# PIC18F4550.net
KiCad netlist of a schematic drawn in Altium Designer
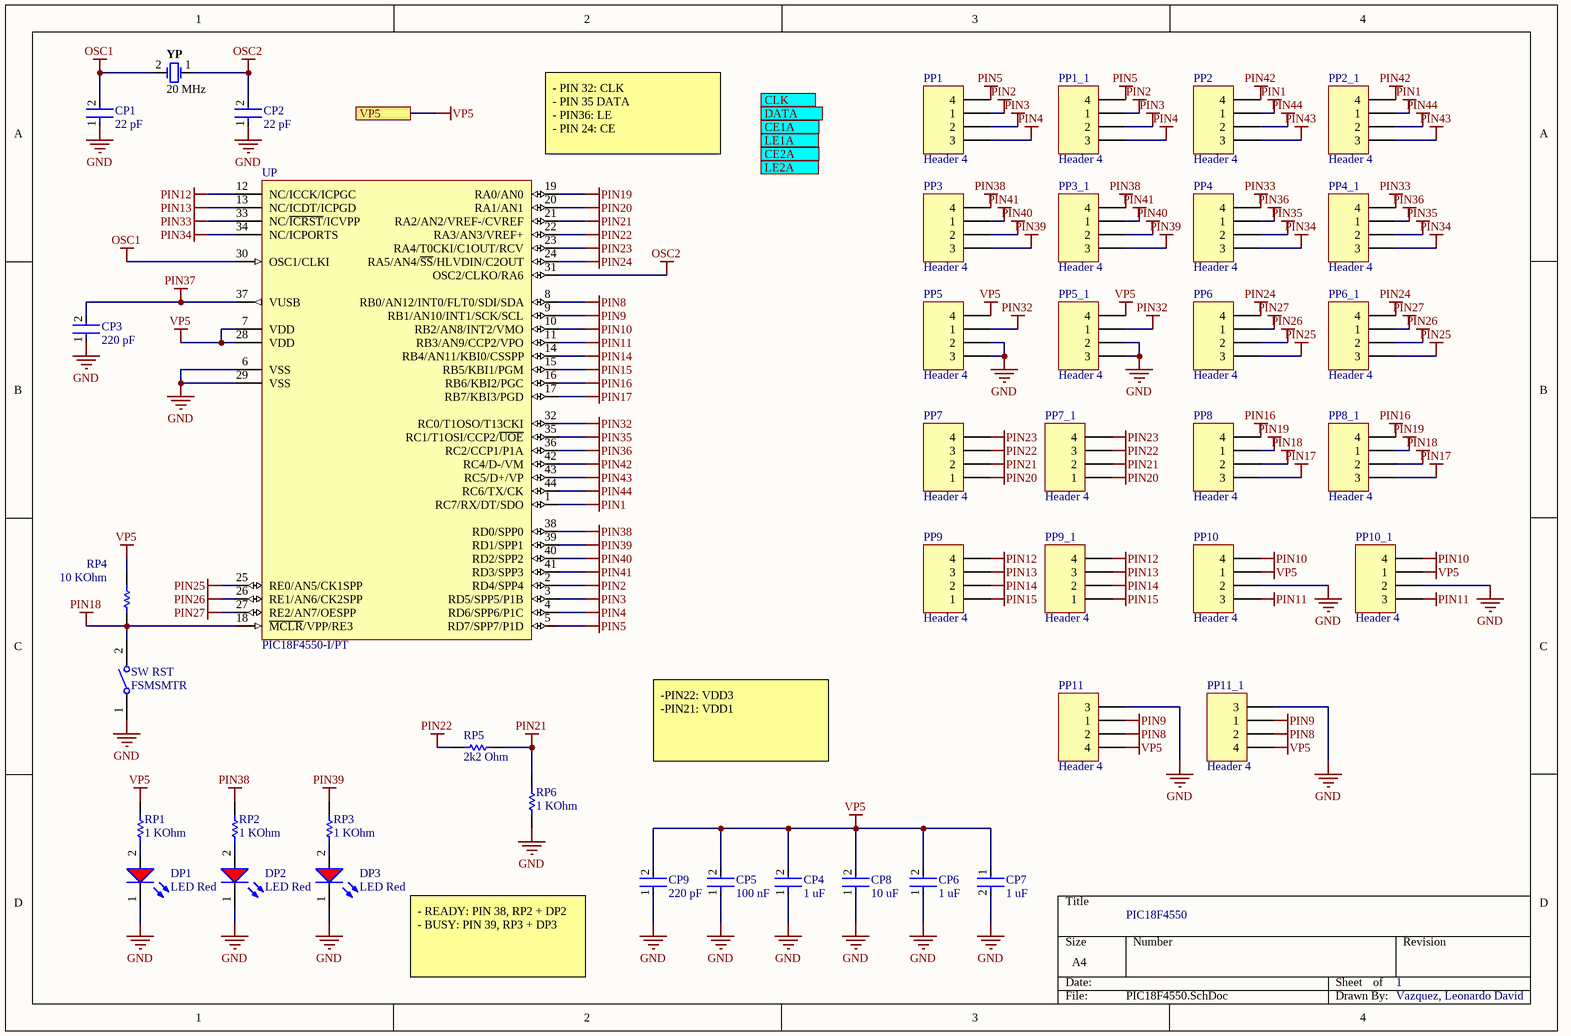
[diagram p0: PIC18F4550.SchDoc]

(export (version "E")
  (design (tool "Eeschema 10.0.6"))
  (components
    (comp (ref "CP1")
      (value "22 pF")
      (footprint "FP-CC0805-0_85-MFG")
      (description "CAP CER 0.1UF 50V X7R 0805")
      (fields (field (name "TOLERANCE") "0.1") (field (name "MANUFACTURER PART NUMBER") "CC0805KRX7R9BB104"))
      (libsource (lib "Altium Content Vault") (part "11868f565c42a9108669ba33697ecf6"))
    )
    (comp (ref "CP2")
      (value "22 pF")
      (footprint "FP-CC0805-0_85-MFG")
      (description "CAP CER 0.1UF 50V X7R 0805")
      (fields (field (name "TOLERANCE") "0.1") (field (name "MANUFACTURER PART NUMBER") "CC0805KRX7R9BB104"))
      (libsource (lib "Altium Content Vault") (part "11868f565c42a9108669ba33697ecf6"))
    )
    (comp (ref "CP3")
      (value "220 pF")
      (footprint "FP-CC0805-0_85-MFG")
      (description "CAP CER 0.1UF 50V X7R 0805")
      (fields (field (name "TOLERANCE") "0.1") (field (name "MANUFACTURER PART NUMBER") "CC0805KRX7R9BB104"))
      (libsource (lib "Altium Content Vault") (part "11868f565c42a9108669ba33697ecf6"))
    )
    (comp (ref "CP4")
      (value "1 uF")
      (footprint "FP-CC0805-0_85-MFG")
      (description "CAP CER 0.1UF 50V X7R 0805")
      (fields (field (name "TOLERANCE") "0.1") (field (name "MANUFACTURER PART NUMBER") "CC0805KRX7R9BB104"))
      (libsource (lib "Altium Content Vault") (part "11868f565c42a9108669ba33697ecf6"))
    )
    (comp (ref "CP5")
      (value "100 nF")
      (footprint "FP-CC0805-0_85-MFG")
      (description "CAP CER 0.1UF 50V X7R 0805")
      (fields (field (name "TOLERANCE") "0.1") (field (name "MANUFACTURER PART NUMBER") "CC0805KRX7R9BB104"))
      (libsource (lib "Altium Content Vault") (part "11868f565c42a9108669ba33697ecf6"))
    )
    (comp (ref "CP6")
      (value "1 uF")
      (footprint "FP-CC0805-0_85-MFG")
      (description "CAP CER 0.1UF 50V X7R 0805")
      (fields (field (name "TOLERANCE") "0.1") (field (name "MANUFACTURER PART NUMBER") "CC0805KRX7R9BB104"))
      (libsource (lib "Altium Content Vault") (part "11868f565c42a9108669ba33697ecf6"))
    )
    (comp (ref "CP7")
      (value "1 uF")
      (footprint "FP-CC0805-0_85-MFG")
      (description "CAP CER 0.1UF 50V X7R 0805")
      (fields (field (name "TOLERANCE") "0.1") (field (name "MANUFACTURER PART NUMBER") "CC0805KRX7R9BB104"))
      (libsource (lib "") (part "11868f565c42a9108669ba33697ecf6_1"))
    )
    (comp (ref "CP8")
      (value "10 uF")
      (footprint "FP-CC0805-0_85-MFG")
      (description "CAP CER 0.1UF 50V X7R 0805")
      (fields (field (name "TOLERANCE") "0.1") (field (name "MANUFACTURER PART NUMBER") "CC0805KRX7R9BB104"))
      (libsource (lib "Altium Content Vault") (part "11868f565c42a9108669ba33697ecf6"))
    )
    (comp (ref "CP9")
      (value "220 pF")
      (footprint "FP-CC0805-0_85-MFG")
      (description "CAP CER 0.1UF 50V X7R 0805")
      (fields (field (name "TOLERANCE") "0.1") (field (name "MANUFACTURER PART NUMBER") "CC0805KRX7R9BB104"))
      (libsource (lib "Altium Content Vault") (part "11868f565c42a9108669ba33697ecf6"))
    )
    (comp (ref "DP1")
      (value "LED Red")
      (footprint "WL-SMCW_0805_150080xx75000")
      (libsource (lib "Altium Content Vault") (part "LED_Red_2A-1K"))
    )
    (comp (ref "DP2")
      (value "LED Red")
      (footprint "WL-SMCW_0805_150080xx75000")
      (libsource (lib "Altium Content Vault") (part "LED_Red_2A-1K"))
    )
    (comp (ref "DP3")
      (value "LED Red")
      (footprint "WL-SMCW_0805_150080xx75000")
      (libsource (lib "Altium Content Vault") (part "LED_Red_2A-1K"))
    )
    (comp (ref "PP1")
      (value "Header 4")
      (footprint "HDR1X4")
      (description "Header, 4-Pin")
      (fields (field (name "PUBLISHER") "Altium Limited"))
      (libsource (lib "Miscellaneous Connectors") (part "Header 4"))
    )
    (comp (ref "PP1_1")
      (value "Header 4")
      (footprint "HDR1X4")
      (description "Header, 4-Pin")
      (fields (field (name "PUBLISHER") "Altium Limited"))
      (libsource (lib "Miscellaneous Connectors") (part "Header 4"))
    )
    (comp (ref "PP2")
      (value "Header 4")
      (footprint "HDR1X4")
      (description "Header, 4-Pin")
      (fields (field (name "PUBLISHER") "Altium Limited"))
      (libsource (lib "Miscellaneous Connectors") (part "Header 4"))
    )
    (comp (ref "PP2_1")
      (value "Header 4")
      (footprint "HDR1X4")
      (description "Header, 4-Pin")
      (fields (field (name "PUBLISHER") "Altium Limited"))
      (libsource (lib "Miscellaneous Connectors") (part "Header 4"))
    )
    (comp (ref "PP3")
      (value "Header 4")
      (footprint "HDR1X4")
      (description "Header, 4-Pin")
      (fields (field (name "PUBLISHER") "Altium Limited"))
      (libsource (lib "Miscellaneous Connectors") (part "Header 4"))
    )
    (comp (ref "PP3_1")
      (value "Header 4")
      (footprint "HDR1X4")
      (description "Header, 4-Pin")
      (fields (field (name "PUBLISHER") "Altium Limited"))
      (libsource (lib "Miscellaneous Connectors") (part "Header 4"))
    )
    (comp (ref "PP4")
      (value "Header 4")
      (footprint "HDR1X4")
      (description "Header, 4-Pin")
      (fields (field (name "PUBLISHER") "Altium Limited"))
      (libsource (lib "Miscellaneous Connectors") (part "Header 4"))
    )
    (comp (ref "PP4_1")
      (value "Header 4")
      (footprint "HDR1X4")
      (description "Header, 4-Pin")
      (fields (field (name "PUBLISHER") "Altium Limited"))
      (libsource (lib "Miscellaneous Connectors") (part "Header 4"))
    )
    (comp (ref "PP5")
      (value "Header 4")
      (footprint "HDR1X4")
      (description "Header, 4-Pin")
      (fields (field (name "PUBLISHER") "Altium Limited"))
      (libsource (lib "Miscellaneous Connectors") (part "Header 4"))
    )
    (comp (ref "PP5_1")
      (value "Header 4")
      (footprint "HDR1X4")
      (description "Header, 4-Pin")
      (fields (field (name "PUBLISHER") "Altium Limited"))
      (libsource (lib "Miscellaneous Connectors") (part "Header 4"))
    )
    (comp (ref "PP6")
      (value "Header 4")
      (footprint "HDR1X4")
      (description "Header, 4-Pin")
      (fields (field (name "PUBLISHER") "Altium Limited"))
      (libsource (lib "Miscellaneous Connectors") (part "Header 4"))
    )
    (comp (ref "PP6_1")
      (value "Header 4")
      (footprint "HDR1X4")
      (description "Header, 4-Pin")
      (fields (field (name "PUBLISHER") "Altium Limited"))
      (libsource (lib "Miscellaneous Connectors") (part "Header 4"))
    )
    (comp (ref "PP7")
      (value "Header 4")
      (footprint "HDR1X4")
      (description "Header, 4-Pin")
      (fields (field (name "PUBLISHER") "Altium Limited"))
      (libsource (lib "") (part "Header 4_2"))
    )
    (comp (ref "PP7_1")
      (value "Header 4")
      (footprint "HDR1X4")
      (description "Header, 4-Pin")
      (fields (field (name "PUBLISHER") "Altium Limited"))
      (libsource (lib "") (part "Header 4_2"))
    )
    (comp (ref "PP8")
      (value "Header 4")
      (footprint "HDR1X4")
      (description "Header, 4-Pin")
      (fields (field (name "PUBLISHER") "Altium Limited"))
      (libsource (lib "Miscellaneous Connectors") (part "Header 4"))
    )
    (comp (ref "PP8_1")
      (value "Header 4")
      (footprint "HDR1X4")
      (description "Header, 4-Pin")
      (fields (field (name "PUBLISHER") "Altium Limited"))
      (libsource (lib "Miscellaneous Connectors") (part "Header 4"))
    )
    (comp (ref "PP9")
      (value "Header 4")
      (footprint "HDR1X4")
      (description "Header, 4-Pin")
      (fields (field (name "PUBLISHER") "Altium Limited"))
      (libsource (lib "") (part "Header 4_2"))
    )
    (comp (ref "PP9_1")
      (value "Header 4")
      (footprint "HDR1X4")
      (description "Header, 4-Pin")
      (fields (field (name "PUBLISHER") "Altium Limited"))
      (libsource (lib "") (part "Header 4_2"))
    )
    (comp (ref "PP10")
      (value "Header 4")
      (footprint "HDR1X4")
      (description "Header, 4-Pin")
      (fields (field (name "PUBLISHER") "Altium Limited"))
      (libsource (lib "Miscellaneous Connectors") (part "Header 4"))
    )
    (comp (ref "PP10_1")
      (value "Header 4")
      (footprint "HDR1X4")
      (description "Header, 4-Pin")
      (fields (field (name "PUBLISHER") "Altium Limited"))
      (libsource (lib "Miscellaneous Connectors") (part "Header 4"))
    )
    (comp (ref "PP11")
      (value "Header 4")
      (footprint "HDR1X4")
      (description "Header, 4-Pin")
      (fields (field (name "PUBLISHER") "Altium Limited"))
      (libsource (lib "") (part "Header 4_1"))
    )
    (comp (ref "PP11_1")
      (value "Header 4")
      (footprint "HDR1X4")
      (description "Header, 4-Pin")
      (fields (field (name "PUBLISHER") "Altium Limited"))
      (libsource (lib "") (part "Header 4_1"))
    )
    (comp (ref "RP1")
      (value "1 KOhm")
      (footprint "RESC2013X60X40ML20T25")
      (fields (field (name "MANUFACTURER") "Panasonic") (field (name "PART NUMBER") "ERA6AEB101V"))
      (libsource (lib "Altium Content Vault") (part "RES"))
    )
    (comp (ref "RP2")
      (value "1 KOhm")
      (footprint "RESC2013X60X40ML20T25")
      (fields (field (name "MANUFACTURER") "Panasonic") (field (name "PART NUMBER") "ERA6AEB101V"))
      (libsource (lib "Altium Content Vault") (part "RES"))
    )
    (comp (ref "RP3")
      (value "1 KOhm")
      (footprint "RESC2013X60X40ML20T25")
      (fields (field (name "MANUFACTURER") "Panasonic") (field (name "PART NUMBER") "ERA6AEB101V"))
      (libsource (lib "Altium Content Vault") (part "RES"))
    )
    (comp (ref "RP4")
      (value "10 KOhm")
      (footprint "RESC2013X60X40ML20T25")
      (fields (field (name "MANUFACTURER") "Panasonic") (field (name "PART NUMBER") "ERA6AEB101V"))
      (libsource (lib "Altium Content Vault") (part "RES"))
    )
    (comp (ref "RP5")
      (value "2k2 Ohm")
      (footprint "RESC2013X60X40ML20T25")
      (fields (field (name "MANUFACTURER") "Panasonic") (field (name "PART NUMBER") "ERA6AEB101V"))
      (libsource (lib "Altium Content Vault") (part "RES"))
    )
    (comp (ref "RP6")
      (value "1 KOhm")
      (footprint "RESC2013X60X40ML20T25")
      (fields (field (name "MANUFACTURER") "Panasonic") (field (name "PART NUMBER") "ERA6AEB101V"))
      (libsource (lib "Altium Content Vault") (part "RES"))
    )
    (comp (ref "SW RST")
      (value "FSMSMTR")
      (footprint "TECO-FSMSMTR_V")
      (description "FSMSM Push Button Switch, 50 mA, -35 to 85 degC, 2-Pin SMD, RoHS, Tape and Reel")
      (fields (field (name "MANUFACTURER") "TE Connectivity"))
      (libsource (lib "Altium Content Vault") (part "SW-SPST-2_C"))
    )
    (comp (ref "UP")
      (value "PIC18F4550-I/PT")
      (footprint "TQFP-PT44_M")
      (libsource (lib "Altium Content Vault") (part "MC-8B-18F4550-SQ44A"))
    )
    (comp (ref "YP")
      (value "20 MHz")
      (footprint "FOX-FOXSLF160-20")
      (description "Resistance Weld Thru-Hole Crystal, 16 MHz, -20 to 70 degC, 2-Pin THD, RoHS, Bulk")
      (fields (field (name "TOLERANCE") "1%"))
      (libsource (lib "Altium Content Vault") (part "XTAL-1-2-2"))
    )
  )
  (nets
    (net (code "7") (name "GND") (class "Default")
      (node (ref "CP1") (pin "1") (pinfunction "1_1") (pintype "passive"))
      (node (ref "CP2") (pin "1") (pinfunction "1_1") (pintype "passive"))
      (node (ref "CP3") (pin "1") (pinfunction "1_1") (pintype "passive"))
      (node (ref "CP4") (pin "1") (pinfunction "1_1") (pintype "passive"))
      (node (ref "CP5") (pin "1") (pinfunction "1_1") (pintype "passive"))
      (node (ref "CP6") (pin "1") (pinfunction "1_1") (pintype "passive"))
      (node (ref "CP7") (pin "2") (pinfunction "2_2") (pintype "passive"))
      (node (ref "CP8") (pin "1") (pinfunction "1_1") (pintype "passive"))
      (node (ref "CP9") (pin "1") (pinfunction "1_1") (pintype "passive"))
      (node (ref "DP1") (pin "1") (pinfunction "K_1") (pintype "passive"))
      (node (ref "DP2") (pin "1") (pinfunction "K_1") (pintype "passive"))
      (node (ref "DP3") (pin "1") (pinfunction "K_1") (pintype "passive"))
      (node (ref "PP10") (pin "2") (pinfunction "2_2") (pintype "passive"))
      (node (ref "PP10_1") (pin "2") (pinfunction "2_2") (pintype "passive"))
      (node (ref "PP11") (pin "3") (pinfunction "3_3") (pintype "passive"))
      (node (ref "PP11_1") (pin "3") (pinfunction "3_3") (pintype "passive"))
      (node (ref "PP5") (pin "2") (pinfunction "2_2") (pintype "passive"))
      (node (ref "PP5") (pin "3") (pinfunction "3_3") (pintype "passive"))
      (node (ref "PP5_1") (pin "2") (pinfunction "2_2") (pintype "passive"))
      (node (ref "PP5_1") (pin "3") (pinfunction "3_3") (pintype "passive"))
      (node (ref "RP6") (pin "1") (pinfunction "1_1") (pintype "passive"))
      (node (ref "SW RST") (pin "1") (pinfunction "1_1") (pintype "passive"))
      (node (ref "UP") (pin "29") (pinfunction "VSS_29") (pintype "power_in"))
      (node (ref "UP") (pin "6") (pinfunction "VSS_6") (pintype "power_in"))
    )
    (net (code "8") (name "Net-(DP1-A)") (class "Default")
      (node (ref "DP1") (pin "2") (pinfunction "A_2") (pintype "passive"))
      (node (ref "RP1") (pin "1") (pinfunction "1_1") (pintype "passive"))
    )
    (net (code "9") (name "Net-(DP2-A)") (class "Default")
      (node (ref "DP2") (pin "2") (pinfunction "A_2") (pintype "passive"))
      (node (ref "RP2") (pin "1") (pinfunction "1_1") (pintype "passive"))
    )
    (net (code "10") (name "Net-(DP3-A)") (class "Default")
      (node (ref "DP3") (pin "2") (pinfunction "A_2") (pintype "passive"))
      (node (ref "RP3") (pin "1") (pinfunction "1_1") (pintype "passive"))
    )
    (net (code "11") (name "OSC1") (class "Default")
      (node (ref "CP1") (pin "2") (pinfunction "2_2") (pintype "passive"))
      (node (ref "UP") (pin "30") (pinfunction "OSC1/CLKI_30") (pintype "input"))
      (node (ref "YP") (pin "2") (pinfunction "2_2") (pintype "passive"))
    )
    (net (code "12") (name "OSC2") (class "Default")
      (node (ref "CP2") (pin "2") (pinfunction "2_2") (pintype "passive"))
      (node (ref "UP") (pin "31") (pinfunction "OSC2/CLKO/RA6_31") (pintype "bidirectional"))
      (node (ref "YP") (pin "1") (pinfunction "1_1") (pintype "passive"))
    )
    (net (code "13") (name "PIN1") (class "Default")
      (node (ref "PP2") (pin "1") (pinfunction "1_1") (pintype "passive"))
      (node (ref "PP2_1") (pin "1") (pinfunction "1_1") (pintype "passive"))
      (node (ref "UP") (pin "1") (pinfunction "RC7/RX/DT/SDO_1") (pintype "bidirectional"))
    )
    (net (code "14") (name "PIN2") (class "Default")
      (node (ref "PP1") (pin "1") (pinfunction "1_1") (pintype "passive"))
      (node (ref "PP1_1") (pin "1") (pinfunction "1_1") (pintype "passive"))
      (node (ref "UP") (pin "2") (pinfunction "RD4/SPP4_2") (pintype "bidirectional"))
    )
    (net (code "15") (name "PIN3") (class "Default")
      (node (ref "PP1") (pin "2") (pinfunction "2_2") (pintype "passive"))
      (node (ref "PP1_1") (pin "2") (pinfunction "2_2") (pintype "passive"))
      (node (ref "UP") (pin "3") (pinfunction "RD5/SPP5/P1B_3") (pintype "bidirectional"))
    )
    (net (code "16") (name "PIN4") (class "Default")
      (node (ref "PP1") (pin "3") (pinfunction "3_3") (pintype "passive"))
      (node (ref "PP1_1") (pin "3") (pinfunction "3_3") (pintype "passive"))
      (node (ref "UP") (pin "4") (pinfunction "RD6/SPP6/P1C_4") (pintype "bidirectional"))
    )
    (net (code "17") (name "PIN5") (class "Default")
      (node (ref "PP1") (pin "4") (pinfunction "4_4") (pintype "passive"))
      (node (ref "PP1_1") (pin "4") (pinfunction "4_4") (pintype "passive"))
      (node (ref "UP") (pin "5") (pinfunction "RD7/SPP7/P1D_5") (pintype "bidirectional"))
    )
    (net (code "18") (name "PIN8") (class "Default")
      (node (ref "PP11") (pin "2") (pinfunction "2_2") (pintype "passive"))
      (node (ref "PP11_1") (pin "2") (pinfunction "2_2") (pintype "passive"))
      (node (ref "UP") (pin "8") (pinfunction "RB0/AN12/INT0/FLT0/SDI/SDA_8") (pintype "bidirectional"))
    )
    (net (code "19") (name "PIN9") (class "Default")
      (node (ref "PP11") (pin "1") (pinfunction "1_1") (pintype "passive"))
      (node (ref "PP11_1") (pin "1") (pinfunction "1_1") (pintype "passive"))
      (node (ref "UP") (pin "9") (pinfunction "RB1/AN10/INT1/SCK/SCL_9") (pintype "bidirectional"))
    )
    (net (code "20") (name "PIN10") (class "Default")
      (node (ref "PP10") (pin "4") (pinfunction "4_4") (pintype "passive"))
      (node (ref "PP10_1") (pin "4") (pinfunction "4_4") (pintype "passive"))
      (node (ref "UP") (pin "10") (pinfunction "RB2/AN8/INT2/VMO_10") (pintype "bidirectional"))
    )
    (net (code "21") (name "PIN11") (class "Default")
      (node (ref "PP10") (pin "3") (pinfunction "3_3") (pintype "passive"))
      (node (ref "PP10_1") (pin "3") (pinfunction "3_3") (pintype "passive"))
      (node (ref "UP") (pin "11") (pinfunction "RB3/AN9/CCP2/VPO_11") (pintype "bidirectional"))
    )
    (net (code "22") (name "PIN12") (class "Default")
      (node (ref "PP9") (pin "4") (pinfunction "4_4") (pintype "passive"))
      (node (ref "PP9_1") (pin "4") (pinfunction "4_4") (pintype "passive"))
      (node (ref "UP") (pin "12") (pinfunction "NC/ICCK/ICPGC_12") (pintype "passive"))
    )
    (net (code "23") (name "PIN13") (class "Default")
      (node (ref "PP9") (pin "3") (pinfunction "3_3") (pintype "passive"))
      (node (ref "PP9_1") (pin "3") (pinfunction "3_3") (pintype "passive"))
      (node (ref "UP") (pin "13") (pinfunction "NC/ICDT/ICPGD_13") (pintype "passive"))
    )
    (net (code "24") (name "PIN14") (class "Default")
      (node (ref "PP9") (pin "2") (pinfunction "2_2") (pintype "passive"))
      (node (ref "PP9_1") (pin "2") (pinfunction "2_2") (pintype "passive"))
      (node (ref "UP") (pin "14") (pinfunction "RB4/AN11/KBI0/CSSPP_14") (pintype "bidirectional"))
    )
    (net (code "25") (name "PIN15") (class "Default")
      (node (ref "PP9") (pin "1") (pinfunction "1_1") (pintype "passive"))
      (node (ref "PP9_1") (pin "1") (pinfunction "1_1") (pintype "passive"))
      (node (ref "UP") (pin "15") (pinfunction "RB5/KBI1/PGM_15") (pintype "bidirectional"))
    )
    (net (code "26") (name "PIN16") (class "Default")
      (node (ref "PP8") (pin "4") (pinfunction "4_4") (pintype "passive"))
      (node (ref "PP8_1") (pin "4") (pinfunction "4_4") (pintype "passive"))
      (node (ref "UP") (pin "16") (pinfunction "RB6/KBI2/PGC_16") (pintype "bidirectional"))
    )
    (net (code "27") (name "PIN17") (class "Default")
      (node (ref "PP8") (pin "3") (pinfunction "3_3") (pintype "passive"))
      (node (ref "PP8_1") (pin "3") (pinfunction "3_3") (pintype "passive"))
      (node (ref "UP") (pin "17") (pinfunction "RB7/KBI3/PGD_17") (pintype "bidirectional"))
    )
    (net (code "28") (name "PIN18") (class "Default")
      (node (ref "PP8") (pin "2") (pinfunction "2_2") (pintype "passive"))
      (node (ref "PP8_1") (pin "2") (pinfunction "2_2") (pintype "passive"))
      (node (ref "RP4") (pin "1") (pinfunction "1_1") (pintype "passive"))
      (node (ref "SW RST") (pin "2") (pinfunction "2_2") (pintype "passive"))
      (node (ref "UP") (pin "18") (pinfunction "~{MCLR}/VPP/RE3_18") (pintype "input"))
    )
    (net (code "29") (name "PIN19") (class "Default")
      (node (ref "PP8") (pin "1") (pinfunction "1_1") (pintype "passive"))
      (node (ref "PP8_1") (pin "1") (pinfunction "1_1") (pintype "passive"))
      (node (ref "UP") (pin "19") (pinfunction "RA0/AN0_19") (pintype "bidirectional"))
    )
    (net (code "30") (name "PIN20") (class "Default")
      (node (ref "PP7") (pin "1") (pinfunction "1_1") (pintype "passive"))
      (node (ref "PP7_1") (pin "1") (pinfunction "1_1") (pintype "passive"))
      (node (ref "UP") (pin "20") (pinfunction "RA1/AN1_20") (pintype "bidirectional"))
    )
    (net (code "31") (name "PIN21") (class "Default")
      (node (ref "PP7") (pin "2") (pinfunction "2_2") (pintype "passive"))
      (node (ref "PP7_1") (pin "2") (pinfunction "2_2") (pintype "passive"))
      (node (ref "RP5") (pin "1") (pinfunction "1_1") (pintype "passive"))
      (node (ref "RP6") (pin "2") (pinfunction "2_2") (pintype "passive"))
      (node (ref "UP") (pin "21") (pinfunction "RA2/AN2/VREF-/CVREF_21") (pintype "bidirectional"))
    )
    (net (code "32") (name "PIN22") (class "Default")
      (node (ref "PP7") (pin "3") (pinfunction "3_3") (pintype "passive"))
      (node (ref "PP7_1") (pin "3") (pinfunction "3_3") (pintype "passive"))
      (node (ref "RP5") (pin "2") (pinfunction "2_2") (pintype "passive"))
      (node (ref "UP") (pin "22") (pinfunction "RA3/AN3/VREF+_22") (pintype "bidirectional"))
    )
    (net (code "33") (name "PIN23") (class "Default")
      (node (ref "PP7") (pin "4") (pinfunction "4_4") (pintype "passive"))
      (node (ref "PP7_1") (pin "4") (pinfunction "4_4") (pintype "passive"))
      (node (ref "UP") (pin "23") (pinfunction "RA4/T0CKI/C1OUT/RCV_23") (pintype "bidirectional"))
    )
    (net (code "34") (name "PIN24") (class "Default")
      (node (ref "PP6") (pin "4") (pinfunction "4_4") (pintype "passive"))
      (node (ref "PP6_1") (pin "4") (pinfunction "4_4") (pintype "passive"))
      (node (ref "UP") (pin "24") (pinfunction "RA5/AN4/~{SS}/HLVDIN/C2OUT_24") (pintype "bidirectional"))
    )
    (net (code "35") (name "PIN25") (class "Default")
      (node (ref "PP6") (pin "3") (pinfunction "3_3") (pintype "passive"))
      (node (ref "PP6_1") (pin "3") (pinfunction "3_3") (pintype "passive"))
      (node (ref "UP") (pin "25") (pinfunction "RE0/AN5/CK1SPP_25") (pintype "bidirectional"))
    )
    (net (code "36") (name "PIN26") (class "Default")
      (node (ref "PP6") (pin "2") (pinfunction "2_2") (pintype "passive"))
      (node (ref "PP6_1") (pin "2") (pinfunction "2_2") (pintype "passive"))
      (node (ref "UP") (pin "26") (pinfunction "RE1/AN6/CK2SPP_26") (pintype "bidirectional"))
    )
    (net (code "37") (name "PIN27") (class "Default")
      (node (ref "PP6") (pin "1") (pinfunction "1_1") (pintype "passive"))
      (node (ref "PP6_1") (pin "1") (pinfunction "1_1") (pintype "passive"))
      (node (ref "UP") (pin "27") (pinfunction "RE2/AN7/OESPP_27") (pintype "bidirectional"))
    )
    (net (code "38") (name "PIN32") (class "Default")
      (node (ref "PP5") (pin "1") (pinfunction "1_1") (pintype "passive"))
      (node (ref "PP5_1") (pin "1") (pinfunction "1_1") (pintype "passive"))
      (node (ref "UP") (pin "32") (pinfunction "RC0/T1OSO/T13CKI_32") (pintype "bidirectional"))
    )
    (net (code "39") (name "PIN33") (class "Default")
      (node (ref "PP4") (pin "4") (pinfunction "4_4") (pintype "passive"))
      (node (ref "PP4_1") (pin "4") (pinfunction "4_4") (pintype "passive"))
      (node (ref "UP") (pin "33") (pinfunction "NC/~{ICRST}/ICVPP_33") (pintype "passive"))
    )
    (net (code "40") (name "PIN34") (class "Default")
      (node (ref "PP4") (pin "3") (pinfunction "3_3") (pintype "passive"))
      (node (ref "PP4_1") (pin "3") (pinfunction "3_3") (pintype "passive"))
      (node (ref "UP") (pin "34") (pinfunction "NC/ICPORTS_34") (pintype "passive"))
    )
    (net (code "41") (name "PIN35") (class "Default")
      (node (ref "PP4") (pin "2") (pinfunction "2_2") (pintype "passive"))
      (node (ref "PP4_1") (pin "2") (pinfunction "2_2") (pintype "passive"))
      (node (ref "UP") (pin "35") (pinfunction "RC1/T1OSI/CCP2/~{UOE}_35") (pintype "bidirectional"))
    )
    (net (code "42") (name "PIN36") (class "Default")
      (node (ref "PP4") (pin "1") (pinfunction "1_1") (pintype "passive"))
      (node (ref "PP4_1") (pin "1") (pinfunction "1_1") (pintype "passive"))
      (node (ref "UP") (pin "36") (pinfunction "RC2/CCP1/P1A_36") (pintype "bidirectional"))
    )
    (net (code "43") (name "PIN37") (class "Default")
      (node (ref "CP3") (pin "2") (pinfunction "2_2") (pintype "passive"))
      (node (ref "UP") (pin "37") (pinfunction "VUSB_37") (pintype "output"))
    )
    (net (code "44") (name "PIN38") (class "Default")
      (node (ref "PP3") (pin "4") (pinfunction "4_4") (pintype "passive"))
      (node (ref "PP3_1") (pin "4") (pinfunction "4_4") (pintype "passive"))
      (node (ref "RP2") (pin "2") (pinfunction "2_2") (pintype "passive"))
      (node (ref "UP") (pin "38") (pinfunction "RD0/SPP0_38") (pintype "bidirectional"))
    )
    (net (code "45") (name "PIN39") (class "Default")
      (node (ref "PP3") (pin "3") (pinfunction "3_3") (pintype "passive"))
      (node (ref "PP3_1") (pin "3") (pinfunction "3_3") (pintype "passive"))
      (node (ref "RP3") (pin "2") (pinfunction "2_2") (pintype "passive"))
      (node (ref "UP") (pin "39") (pinfunction "RD1/SPP1_39") (pintype "bidirectional"))
    )
    (net (code "46") (name "PIN40") (class "Default")
      (node (ref "PP3") (pin "2") (pinfunction "2_2") (pintype "passive"))
      (node (ref "PP3_1") (pin "2") (pinfunction "2_2") (pintype "passive"))
      (node (ref "UP") (pin "40") (pinfunction "RD2/SPP2_40") (pintype "bidirectional"))
    )
    (net (code "47") (name "PIN41") (class "Default")
      (node (ref "PP3") (pin "1") (pinfunction "1_1") (pintype "passive"))
      (node (ref "PP3_1") (pin "1") (pinfunction "1_1") (pintype "passive"))
      (node (ref "UP") (pin "41") (pinfunction "RD3/SPP3_41") (pintype "bidirectional"))
    )
    (net (code "48") (name "PIN42") (class "Default")
      (node (ref "PP2") (pin "4") (pinfunction "4_4") (pintype "passive"))
      (node (ref "PP2_1") (pin "4") (pinfunction "4_4") (pintype "passive"))
      (node (ref "UP") (pin "42") (pinfunction "RC4/D-/VM_42") (pintype "bidirectional"))
    )
    (net (code "49") (name "PIN43") (class "Default")
      (node (ref "PP2") (pin "3") (pinfunction "3_3") (pintype "passive"))
      (node (ref "PP2_1") (pin "3") (pinfunction "3_3") (pintype "passive"))
      (node (ref "UP") (pin "43") (pinfunction "RC5/D+/VP_43") (pintype "bidirectional"))
    )
    (net (code "50") (name "PIN44") (class "Default")
      (node (ref "PP2") (pin "2") (pinfunction "2_2") (pintype "passive"))
      (node (ref "PP2_1") (pin "2") (pinfunction "2_2") (pintype "passive"))
      (node (ref "UP") (pin "44") (pinfunction "RC6/TX/CK_44") (pintype "bidirectional"))
    )
    (net (code "51") (name "VP5") (class "Default")
      (node (ref "CP4") (pin "2") (pinfunction "2_2") (pintype "passive"))
      (node (ref "CP5") (pin "2") (pinfunction "2_2") (pintype "passive"))
      (node (ref "CP6") (pin "2") (pinfunction "2_2") (pintype "passive"))
      (node (ref "CP7") (pin "1") (pinfunction "1_1") (pintype "passive"))
      (node (ref "CP8") (pin "2") (pinfunction "2_2") (pintype "passive"))
      (node (ref "CP9") (pin "2") (pinfunction "2_2") (pintype "passive"))
      (node (ref "PP10") (pin "1") (pinfunction "1_1") (pintype "passive"))
      (node (ref "PP10_1") (pin "1") (pinfunction "1_1") (pintype "passive"))
      (node (ref "PP11") (pin "4") (pinfunction "4_4") (pintype "passive"))
      (node (ref "PP11_1") (pin "4") (pinfunction "4_4") (pintype "passive"))
      (node (ref "PP5") (pin "4") (pinfunction "4_4") (pintype "passive"))
      (node (ref "PP5_1") (pin "4") (pinfunction "4_4") (pintype "passive"))
      (node (ref "RP1") (pin "2") (pinfunction "2_2") (pintype "passive"))
      (node (ref "RP4") (pin "2") (pinfunction "2_2") (pintype "passive"))
      (node (ref "UP") (pin "28") (pinfunction "VDD_28") (pintype "power_in"))
      (node (ref "UP") (pin "7") (pinfunction "VDD_7") (pintype "power_in"))
    )
  )
)
